# zulu_a7_4.net
KiCad netlist of a schematic drawn in Altium Designer
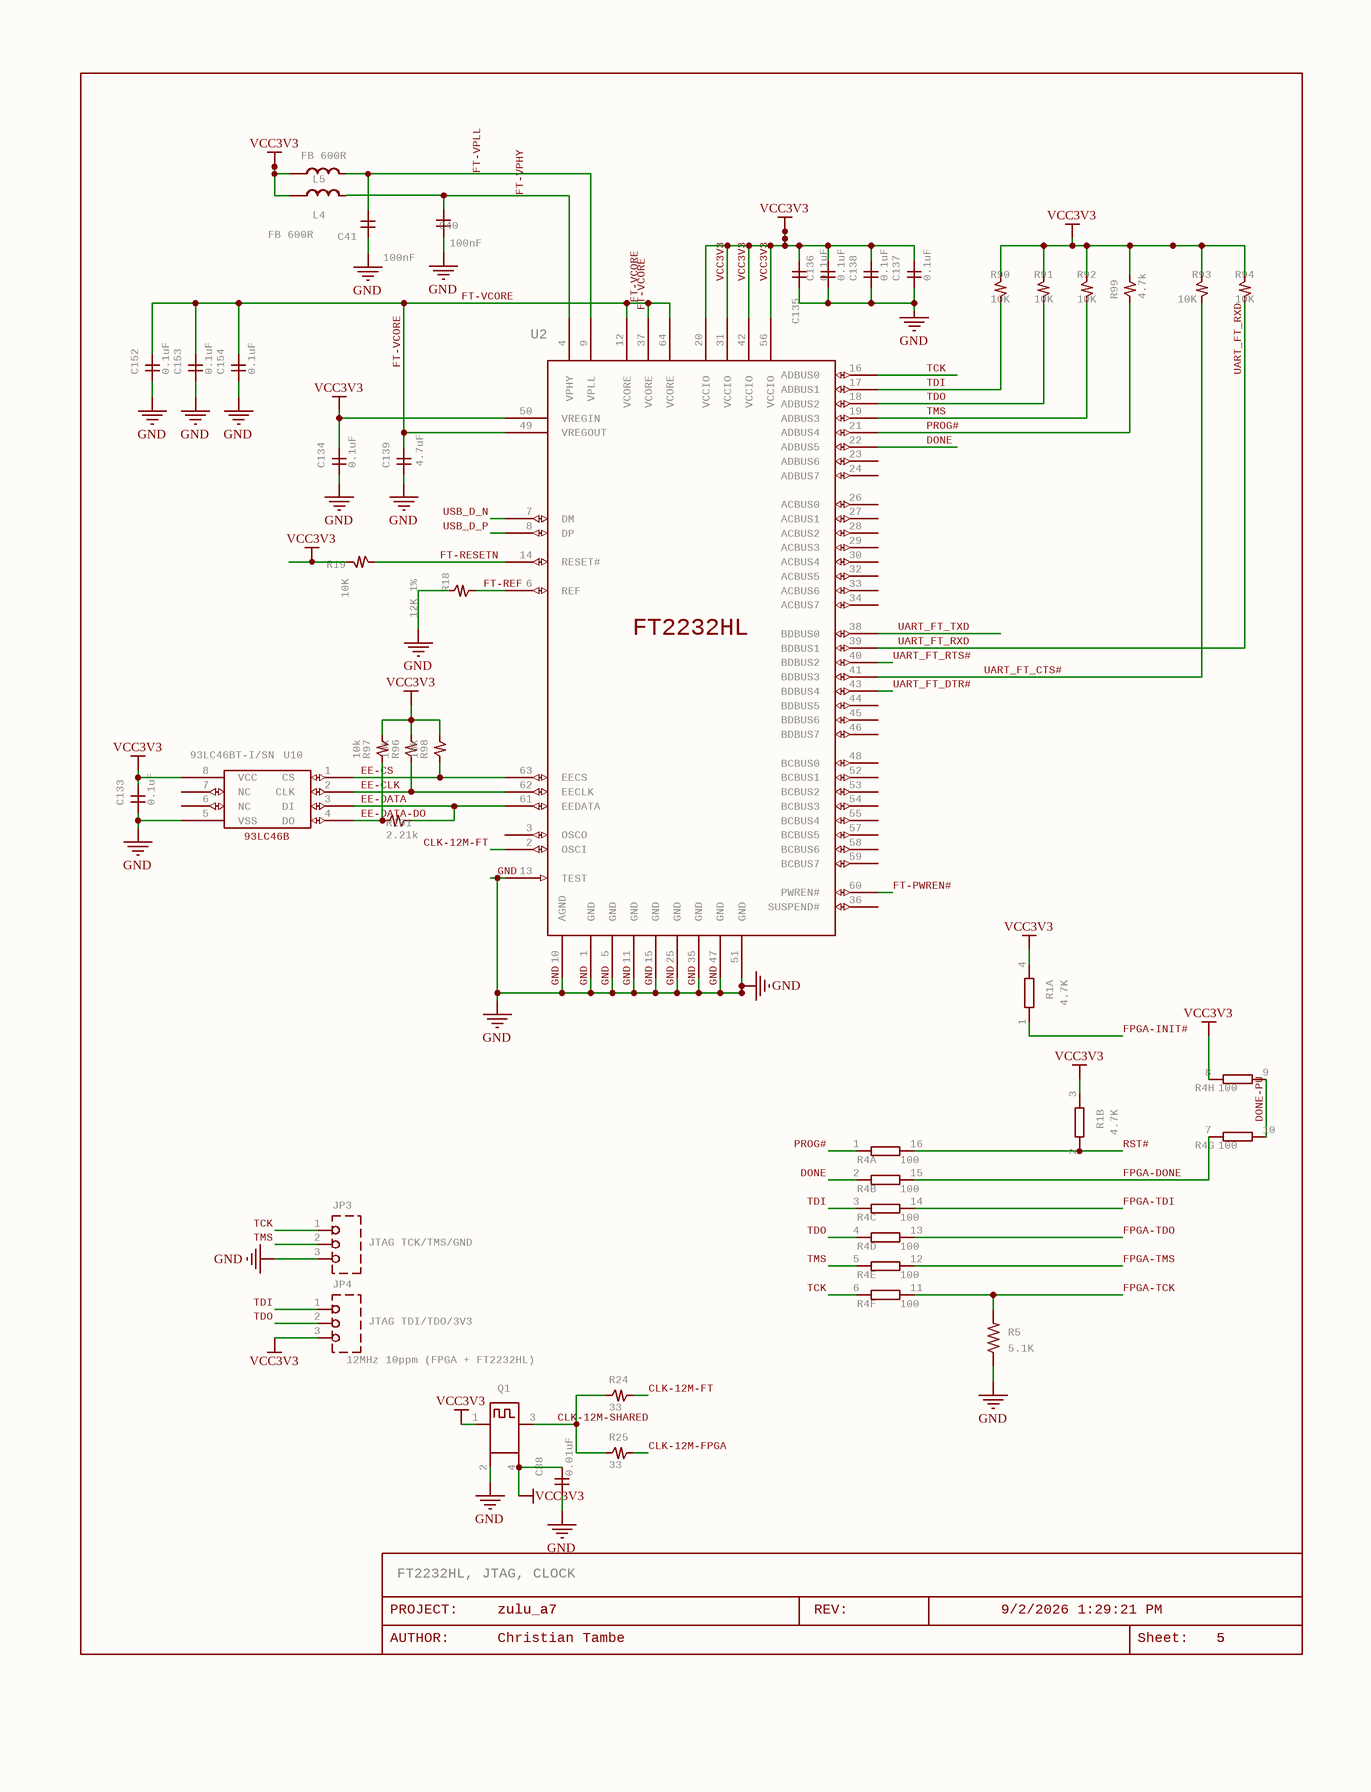
[diagram p0: zulu_a7_4.SchDoc]

(export (version "E")
  (design (tool "Eeschema 10.0.6"))
  (components
    (comp (ref "C38")
      (value "0.01uF")
      (footprint "C0201")
      (description "CAPACITOR, generic non-polarized, horizontal pins")
      (fields (field (name "MANF") "Murata"))
      (libsource (lib "rcl") (part "C-GENERICC0201"))
    )
    (comp (ref "C40")
      (value "100nF")
      (footprint "C0201")
      (description "CAPACITOR, generic non-polarized, horizontal pins")
      (fields (field (name "MANF") "Murata"))
      (libsource (lib "rcl") (part "C-GENERICC0201"))
    )
    (comp (ref "C41")
      (value "100nF")
      (footprint "C0201")
      (description "CAPACITOR, generic non-polarized, horizontal pins")
      (fields (field (name "MANF") "Murata"))
      (libsource (lib "") (part "C-GENERICC0201_2"))
    )
    (comp (ref "C133")
      (value "0.1uF")
      (footprint "C0201")
      (description "CAPACITOR, generic non-polarized, horizontal pins")
      (fields (field (name "MANF") "Murata"))
      (libsource (lib "rcl") (part "C-GENERICC0201"))
    )
    (comp (ref "C134")
      (value "0.1uF")
      (footprint "C0201")
      (description "CAPACITOR, generic non-polarized, horizontal pins")
      (fields (field (name "MANF") "Murata"))
      (libsource (lib "rcl") (part "C-GENERICC0201"))
    )
    (comp (ref "C135")
      (value "0.1uF")
      (footprint "C0201")
      (description "CAPACITOR, generic non-polarized, horizontal pins")
      (fields (field (name "MANF") "Murata"))
      (libsource (lib "rcl") (part "C-GENERICC0201"))
    )
    (comp (ref "C136")
      (value "0.1uF")
      (footprint "C0201")
      (description "CAPACITOR, generic non-polarized, horizontal pins")
      (fields (field (name "MANF") "Murata"))
      (libsource (lib "rcl") (part "C-GENERICC0201"))
    )
    (comp (ref "C137")
      (value "0.1uF")
      (footprint "C0201")
      (description "CAPACITOR, generic non-polarized, horizontal pins")
      (fields (field (name "MANF") "Murata"))
      (libsource (lib "rcl") (part "C-GENERICC0201"))
    )
    (comp (ref "C138")
      (value "0.1uF")
      (footprint "C0201")
      (description "CAPACITOR, generic non-polarized, horizontal pins")
      (fields (field (name "MANF") "Murata"))
      (libsource (lib "rcl") (part "C-GENERICC0201"))
    )
    (comp (ref "C139")
      (value "4.7uF")
      (footprint "C0402")
      (description "CAPACITOR, generic non-polarized, horizontal pins")
      (fields (field (name "MANF") "Taiyo Yuden"))
      (libsource (lib "rcl") (part "C-GENERICC0402"))
    )
    (comp (ref "C152")
      (value "0.1uF")
      (footprint "C0201")
      (description "CAPACITOR, generic non-polarized, horizontal pins")
      (fields (field (name "MANF") "Murata"))
      (libsource (lib "") (part "C-GENERICC0201_1"))
    )
    (comp (ref "C153")
      (value "0.1uF")
      (footprint "C0201")
      (description "CAPACITOR, generic non-polarized, horizontal pins")
      (fields (field (name "MANF") "Murata"))
      (libsource (lib "") (part "C-GENERICC0201_1"))
    )
    (comp (ref "C154")
      (value "0.1uF")
      (footprint "C0201")
      (description "CAPACITOR, generic non-polarized, horizontal pins")
      (fields (field (name "MANF") "Murata"))
      (libsource (lib "") (part "C-GENERICC0201_1"))
    )
    (comp (ref "FRAME4")
      (value "DOCFIELD")
      (description "DOCUMENT FIELD")
      (fields
        (field (name "LAST_DATE_TIME") "9/2/2026 1:29:21 PM")
        (field (name "SHEET") "Sheet:")
        (field (name "SHEET_1") "5")
        (field (name "REV") "REV:")
        (field (name "PROJECT") "PROJECT:")
        (field (name "DRAWING_NAME") "zulu_a7")
        (field (name "AUTHOR") "Christian Tambe")
        (field (name "DRAWING_NAME_1") "zulu_a7")
        (field (name "SHEET_2") "5")
        (field (name "LIBRARYNAME") "ctambe")
      )
      (libsource (lib "ctambe") (part "DOCFIELD"))
    )
    (comp (ref "JP3")
      (value "JTAG TCK/TMS/GND")
      (footprint "1X03-NOSILK")
      (fields (field (name "LIBRARYNAME") "pinhead"))
      (libsource (lib "pinhead") (part "TESTPT-1X3NOSILK"))
    )
    (comp (ref "JP4")
      (value "JTAG TDI/TDO/3V3")
      (footprint "1X03-NOSILK")
      (fields (field (name "LIBRARYNAME") "pinhead"))
      (libsource (lib "pinhead") (part "TESTPT-1X3NOSILK"))
    )
    (comp (ref "L4")
      (value "FB 600R")
      (footprint "IND0603")
      (description "INDUCTOR, generic power inductor")
      (fields (field (name "MANF") "Murata") (field (name "LIBRARYNAME") "ctambe"))
      (libsource (lib "ctambe") (part "INDUCTOR"))
    )
    (comp (ref "L5")
      (value "FB 600R")
      (footprint "IND0603")
      (description "INDUCTOR, generic power inductor")
      (fields (field (name "MANF") "Murata") (field (name "LIBRARYNAME") "ctambe"))
      (libsource (lib "ctambe") (part "INDUCTOR"))
    )
    (comp (ref "Q1")
      (value "12MHz 10ppm (FPGA + FT2232HL)")
      (footprint "32X25")
      (description "Crystal Chip")
      (fields (field (name "MANF") "ECS") (field (name "LIBRARYNAME") "ctambe"))
      (libsource (lib "ctambe") (part "OSC_CHIPASEM1-12MHZ"))
    )
    (comp (ref "R1")
      (value "4.7K")
      (footprint "742C043")
      (description "Resistor 2-pack   Package of two resistors.")
      (fields (field (name "MANF") "CTS") (field (name "LIBRARYNAME") "ctambe"))
      (libsource (lib "ctambe") (part "RES2742"))
    )
    (comp (ref "R4")
      (value "100")
      (footprint "742C163")
      (description "Resistor 8-pack   Package of eight resistors, six used.")
      (fields (field (name "MANF") "CTS") (field (name "LIBRARYNAME") "ctambe"))
      (libsource (lib "ctambe") (part "RES8742"))
    )
    (comp (ref "R5")
      (value "5.1K")
      (footprint "R0201")
      (description "RESISTOR, American symbol")
      (fields (field (name "MANF") "Yageo"))
      (libsource (lib "rcl") (part "R-US_R0201"))
    )
    (comp (ref "R18")
      (value "12K 1%")
      (footprint "R0402")
      (description "RESISTOR, American symbol, small 2-zigzag variant (sheet 2 only)")
      (fields (field (name "MANF") "Yageo"))
      (libsource (lib "rcl") (part "R-US_SMALLR0402"))
    )
    (comp (ref "R19")
      (value "10K")
      (footprint "R0201")
      (description "RESISTOR, American symbol, small 2-zigzag variant (sheet 2 only)")
      (fields (field (name "MANF") "Yageo"))
      (libsource (lib "rcl") (part "R-US_SMALLR0201"))
    )
    (comp (ref "R24")
      (value "33")
      (footprint "R0201")
      (description "RESISTOR, American symbol, small 2-zigzag variant (sheet 2 only)")
      (fields (field (name "MANF") "Yageo"))
      (libsource (lib "rcl") (part "R-US_SMALLR0201"))
    )
    (comp (ref "R25")
      (value "33")
      (footprint "R0201")
      (description "RESISTOR, American symbol, small 2-zigzag variant (sheet 2 only)")
      (fields (field (name "MANF") "Yageo"))
      (libsource (lib "rcl") (part "R-US_SMALLR0201"))
    )
    (comp (ref "R90")
      (value "10K")
      (footprint "R0201")
      (description "RESISTOR, American symbol, small 2-zigzag variant (sheet 2 only)")
      (fields (field (name "MANF") "Yageo"))
      (libsource (lib "rcl") (part "R-US_SMALLR0201"))
    )
    (comp (ref "R91")
      (value "10K")
      (footprint "R0201")
      (description "RESISTOR, American symbol, small 2-zigzag variant (sheet 2 only)")
      (fields (field (name "MANF") "Yageo"))
      (libsource (lib "rcl") (part "R-US_SMALLR0201"))
    )
    (comp (ref "R92")
      (value "10K")
      (footprint "R0201")
      (description "RESISTOR, American symbol, small 2-zigzag variant (sheet 2 only)")
      (fields (field (name "MANF") "Yageo"))
      (libsource (lib "rcl") (part "R-US_SMALLR0201"))
    )
    (comp (ref "R93")
      (value "10K")
      (footprint "R0201")
      (description "RESISTOR, American symbol, small 2-zigzag variant (sheet 2 only)")
      (fields (field (name "MANF") "Yageo"))
      (libsource (lib "rcl") (part "R-US_SMALLR0201"))
    )
    (comp (ref "R94")
      (value "10K")
      (footprint "R0201")
      (description "RESISTOR, American symbol, small 2-zigzag variant (sheet 2 only)")
      (fields (field (name "MANF") "Yageo"))
      (libsource (lib "rcl") (part "R-US_SMALLR0201"))
    )
    (comp (ref "R96")
      (value "10k")
      (footprint "R0201")
      (description "RESISTOR, American symbol, small 2-zigzag variant (sheet 2 only)")
      (fields (field (name "MANF") "Yageo"))
      (libsource (lib "rcl") (part "R-US_SMALLR0201"))
    )
    (comp (ref "R97")
      (value "10k")
      (footprint "R0201")
      (description "RESISTOR, American symbol, small 2-zigzag variant (sheet 2 only)")
      (fields (field (name "MANF") "Yageo"))
      (libsource (lib "rcl") (part "R-US_SMALLR0201"))
    )
    (comp (ref "R98")
      (value "10k")
      (footprint "R0201")
      (description "RESISTOR, American symbol, small 2-zigzag variant (sheet 2 only)")
      (fields (field (name "MANF") "Yageo"))
      (libsource (lib "rcl") (part "R-US_SMALLR0201"))
    )
    (comp (ref "R99")
      (value "4.7k")
      (footprint "R0201")
      (description "RESISTOR, American symbol, small 2-zigzag variant (sheet 2 only)")
      (fields (field (name "MANF") "Yageo"))
      (libsource (lib "rcl") (part "R-US_SMALLR0201"))
    )
    (comp (ref "R101")
      (value "2.21k")
      (footprint "R0201")
      (description "RESISTOR, American symbol, small 2-zigzag variant (sheet 2 only)")
      (fields (field (name "MANF") "Yageo"))
      (libsource (lib "rcl") (part "R-US_SMALLR0201"))
    )
    (comp (ref "U2")
      (value "FT2232HL USB-UART/JTAG Bridge")
      (footprint "FT2232HL-LQFP64")
      (fields
        (field (name "FT2232HL") "FT2232HL")
        (field (name "MANF") "FTDI")
        (field (name "LIBRARYNAME") "ctambe")
      )
      (libsource (lib "ctambe") (part "FT2232HL-LQFP64"))
    )
    (comp (ref "U10")
      (value "93LC46BT-I/SN")
      (footprint "SPI-8_SOIC_150")
      (fields
        (field (name "93LC46B") "93LC46B")
        (field (name "MANF") "Microchip")
        (field (name "LIBRARYNAME") "ctambe")
      )
      (libsource (lib "ctambe") (part "EEPROM-93LC46B-I/SN"))
    )
  )
  (nets
    (net (code "1") (name "/CLK-12M-FPGA") (class "Default")
      (node (ref "R25") (pin "2") (pinfunction "2_2") (pintype "passive"))
    )
    (net (code "2") (name "/CLK-12M-FT") (class "Default")
      (node (ref "R24") (pin "2") (pinfunction "2_2") (pintype "passive"))
      (node (ref "U2") (pin "2") (pinfunction "OSCI_2") (pintype "bidirectional"))
    )
    (net (code "3") (name "/CLK-12M-SHARED") (class "Default")
      (node (ref "Q1") (pin "3") (pinfunction "3_3") (pintype "passive"))
      (node (ref "R24") (pin "1") (pinfunction "1_1") (pintype "passive"))
      (node (ref "R25") (pin "1") (pinfunction "1_1") (pintype "passive"))
    )
    (net (code "4") (name "/DONE") (class "Default")
      (node (ref "R4") (pin "2") (pinfunction "1_2") (pintype "passive"))
      (node (ref "U2") (pin "22") (pinfunction "ADBUS5_22") (pintype "bidirectional"))
    )
    (net (code "5") (name "/DONE-PU") (class "Default")
      (node (ref "R4") (pin "10") (pinfunction "2_10") (pintype "passive"))
      (node (ref "R4") (pin "9") (pinfunction "2_9") (pintype "passive"))
    )
    (net (code "6") (name "/EE-CLK") (class "Default")
      (node (ref "R96") (pin "1") (pinfunction "1_1") (pintype "passive"))
      (node (ref "U10") (pin "2") (pinfunction "CLK_2") (pintype "bidirectional"))
      (node (ref "U2") (pin "62") (pinfunction "EECLK_62") (pintype "bidirectional"))
    )
    (net (code "7") (name "/EE-CS") (class "Default")
      (node (ref "R98") (pin "1") (pinfunction "1_1") (pintype "passive"))
      (node (ref "U10") (pin "1") (pinfunction "CS_1") (pintype "bidirectional"))
      (node (ref "U2") (pin "63") (pinfunction "EECS_63") (pintype "bidirectional"))
    )
    (net (code "8") (name "/EE-DATA") (class "Default")
      (node (ref "R101") (pin "2") (pinfunction "2_2") (pintype "passive"))
      (node (ref "U10") (pin "3") (pinfunction "DI_3") (pintype "bidirectional"))
      (node (ref "U2") (pin "61") (pinfunction "EEDATA_61") (pintype "bidirectional"))
    )
    (net (code "9") (name "/EE-DATA-DO") (class "Default")
      (node (ref "R101") (pin "1") (pinfunction "1_1") (pintype "passive"))
      (node (ref "R97") (pin "1") (pinfunction "1_1") (pintype "passive"))
      (node (ref "U10") (pin "4") (pinfunction "DO_4") (pintype "bidirectional"))
    )
    (net (code "10") (name "/FPGA-DONE") (class "Default")
      (node (ref "R4") (pin "15") (pinfunction "2_15") (pintype "passive"))
      (node (ref "R4") (pin "7") (pinfunction "1_7") (pintype "passive"))
    )
    (net (code "11") (name "/FPGA-INIT#") (class "Default")
      (node (ref "R1") (pin "1") (pinfunction "1_1") (pintype "passive"))
    )
    (net (code "12") (name "/FPGA-TCK") (class "Default")
      (node (ref "R4") (pin "11") (pinfunction "2_11") (pintype "passive"))
      (node (ref "R5") (pin "2") (pinfunction "2_2") (pintype "passive"))
    )
    (net (code "13") (name "/FPGA-TDI") (class "Default")
      (node (ref "R4") (pin "14") (pinfunction "2_14") (pintype "passive"))
    )
    (net (code "14") (name "/FPGA-TDO") (class "Default")
      (node (ref "R4") (pin "13") (pinfunction "2_13") (pintype "passive"))
    )
    (net (code "15") (name "/FPGA-TMS") (class "Default")
      (node (ref "R4") (pin "12") (pinfunction "2_12") (pintype "passive"))
    )
    (net (code "16") (name "/FT-PWREN#") (class "Default")
      (node (ref "U2") (pin "60") (pinfunction "PWREN#_60") (pintype "bidirectional"))
    )
    (net (code "17") (name "/FT-REF") (class "Default")
      (node (ref "R18") (pin "2") (pinfunction "2_2") (pintype "passive"))
      (node (ref "U2") (pin "6") (pinfunction "REF_6") (pintype "bidirectional"))
    )
    (net (code "18") (name "/FT-RESETN") (class "Default")
      (node (ref "R19") (pin "1") (pinfunction "1_1") (pintype "passive"))
      (node (ref "U2") (pin "14") (pinfunction "RESET#_14") (pintype "bidirectional"))
    )
    (net (code "19") (name "/FT-VCORE") (class "Default")
      (node (ref "C139") (pin "2") (pinfunction "2_2") (pintype "passive"))
      (node (ref "C152") (pin "2") (pinfunction "2_2") (pintype "passive"))
      (node (ref "C153") (pin "2") (pinfunction "2_2") (pintype "passive"))
      (node (ref "C154") (pin "2") (pinfunction "2_2") (pintype "passive"))
      (node (ref "U2") (pin "12") (pinfunction "VCORE_12") (pintype "power_in"))
      (node (ref "U2") (pin "37") (pinfunction "VCORE_37") (pintype "power_in"))
      (node (ref "U2") (pin "49") (pinfunction "VREGOUT_49") (pintype "power_in"))
      (node (ref "U2") (pin "64") (pinfunction "VCORE_64") (pintype "power_in"))
    )
    (net (code "20") (name "/FT-VPHY") (class "Default")
      (node (ref "C40") (pin "2") (pinfunction "2_2") (pintype "passive"))
      (node (ref "L4") (pin "1") (pinfunction "1_1") (pintype "passive"))
      (node (ref "U2") (pin "4") (pinfunction "VPHY_4") (pintype "power_in"))
    )
    (net (code "21") (name "/FT-VPLL") (class "Default")
      (node (ref "C41") (pin "2") (pinfunction "2_2") (pintype "passive"))
      (node (ref "L5") (pin "1") (pinfunction "1_1") (pintype "passive"))
      (node (ref "U2") (pin "9") (pinfunction "VPLL_9") (pintype "power_in"))
    )
    (net (code "22") (name "/PROG#") (class "Default")
      (node (ref "R4") (pin "1") (pinfunction "1_1") (pintype "passive"))
      (node (ref "R99") (pin "1") (pinfunction "1_1") (pintype "passive"))
      (node (ref "U2") (pin "21") (pinfunction "ADBUS4_21") (pintype "bidirectional"))
    )
    (net (code "23") (name "/RST#") (class "Default")
      (node (ref "R1") (pin "2") (pinfunction "1_2") (pintype "passive"))
      (node (ref "R4") (pin "16") (pinfunction "2_16") (pintype "passive"))
    )
    (net (code "24") (name "/TCK") (class "Default")
      (node (ref "JP3") (pin "1") (pinfunction "1_1") (pintype "passive"))
      (node (ref "R4") (pin "6") (pinfunction "1_6") (pintype "passive"))
      (node (ref "U2") (pin "16") (pinfunction "ADBUS0_16") (pintype "bidirectional"))
    )
    (net (code "25") (name "/TDI") (class "Default")
      (node (ref "JP4") (pin "1") (pinfunction "1_1") (pintype "passive"))
      (node (ref "R4") (pin "3") (pinfunction "1_3") (pintype "passive"))
      (node (ref "R90") (pin "1") (pinfunction "1_1") (pintype "passive"))
      (node (ref "U2") (pin "17") (pinfunction "ADBUS1_17") (pintype "bidirectional"))
    )
    (net (code "26") (name "/TDO") (class "Default")
      (node (ref "JP4") (pin "2") (pinfunction "2_2") (pintype "passive"))
      (node (ref "R4") (pin "4") (pinfunction "1_4") (pintype "passive"))
      (node (ref "R91") (pin "1") (pinfunction "1_1") (pintype "passive"))
      (node (ref "U2") (pin "18") (pinfunction "ADBUS2_18") (pintype "bidirectional"))
    )
    (net (code "27") (name "/TMS") (class "Default")
      (node (ref "JP3") (pin "2") (pinfunction "2_2") (pintype "passive"))
      (node (ref "R4") (pin "5") (pinfunction "1_5") (pintype "passive"))
      (node (ref "R92") (pin "1") (pinfunction "1_1") (pintype "passive"))
      (node (ref "U2") (pin "19") (pinfunction "ADBUS3_19") (pintype "bidirectional"))
    )
    (net (code "28") (name "/UART_FT_CTS#") (class "Default")
      (node (ref "R93") (pin "1") (pinfunction "1_1") (pintype "passive"))
      (node (ref "U2") (pin "41") (pinfunction "BDBUS3_41") (pintype "bidirectional"))
    )
    (net (code "29") (name "/UART_FT_DTR#") (class "Default")
      (node (ref "U2") (pin "43") (pinfunction "BDBUS4_43") (pintype "bidirectional"))
    )
    (net (code "30") (name "/UART_FT_RTS#") (class "Default")
      (node (ref "U2") (pin "40") (pinfunction "BDBUS2_40") (pintype "bidirectional"))
    )
    (net (code "31") (name "/UART_FT_RXD") (class "Default")
      (node (ref "R94") (pin "1") (pinfunction "1_1") (pintype "passive"))
      (node (ref "U2") (pin "39") (pinfunction "BDBUS1_39") (pintype "bidirectional"))
    )
    (net (code "32") (name "/UART_FT_TXD") (class "Default")
      (node (ref "U2") (pin "38") (pinfunction "BDBUS0_38") (pintype "bidirectional"))
    )
    (net (code "33") (name "/USB_D_N") (class "Default")
      (node (ref "U2") (pin "7") (pinfunction "DM_7") (pintype "bidirectional"))
    )
    (net (code "34") (name "/USB_D_P") (class "Default")
      (node (ref "U2") (pin "8") (pinfunction "DP_8") (pintype "bidirectional"))
    )
    (net (code "35") (name "GND") (class "Default")
      (node (ref "C133") (pin "1") (pinfunction "1_1") (pintype "passive"))
      (node (ref "C134") (pin "1") (pinfunction "1_1") (pintype "passive"))
      (node (ref "C135") (pin "1") (pinfunction "1_1") (pintype "passive"))
      (node (ref "C136") (pin "1") (pinfunction "1_1") (pintype "passive"))
      (node (ref "C137") (pin "1") (pinfunction "1_1") (pintype "passive"))
      (node (ref "C138") (pin "1") (pinfunction "1_1") (pintype "passive"))
      (node (ref "C139") (pin "1") (pinfunction "1_1") (pintype "passive"))
      (node (ref "C152") (pin "1") (pinfunction "1_1") (pintype "passive"))
      (node (ref "C153") (pin "1") (pinfunction "1_1") (pintype "passive"))
      (node (ref "C154") (pin "1") (pinfunction "1_1") (pintype "passive"))
      (node (ref "C38") (pin "1") (pinfunction "1_1") (pintype "passive"))
      (node (ref "C40") (pin "1") (pinfunction "1_1") (pintype "passive"))
      (node (ref "C41") (pin "1") (pinfunction "1_1") (pintype "passive"))
      (node (ref "JP3") (pin "3") (pinfunction "3_3") (pintype "passive"))
      (node (ref "Q1") (pin "2") (pinfunction "2_2") (pintype "passive"))
      (node (ref "R18") (pin "1") (pinfunction "1_1") (pintype "passive"))
      (node (ref "R5") (pin "1") (pinfunction "1_1") (pintype "passive"))
      (node (ref "U10") (pin "5") (pinfunction "VSS_5") (pintype "power_in"))
      (node (ref "U2") (pin "1") (pinfunction "GND_1") (pintype "power_in"))
      (node (ref "U2") (pin "10") (pinfunction "AGND_10") (pintype "power_in"))
      (node (ref "U2") (pin "11") (pinfunction "GND_11") (pintype "power_in"))
      (node (ref "U2") (pin "13") (pinfunction "TEST_13") (pintype "input"))
      (node (ref "U2") (pin "15") (pinfunction "GND_15") (pintype "power_in"))
      (node (ref "U2") (pin "25") (pinfunction "GND_25") (pintype "power_in"))
      (node (ref "U2") (pin "35") (pinfunction "GND_35") (pintype "power_in"))
      (node (ref "U2") (pin "47") (pinfunction "GND_47") (pintype "power_in"))
      (node (ref "U2") (pin "5") (pinfunction "GND_5") (pintype "power_in"))
      (node (ref "U2") (pin "51") (pinfunction "GND_51") (pintype "power_in"))
    )
    (net (code "36") (name "VCC3V3") (class "Default")
      (node (ref "C133") (pin "2") (pinfunction "2_2") (pintype "passive"))
      (node (ref "C134") (pin "2") (pinfunction "2_2") (pintype "passive"))
      (node (ref "C135") (pin "2") (pinfunction "2_2") (pintype "passive"))
      (node (ref "C136") (pin "2") (pinfunction "2_2") (pintype "passive"))
      (node (ref "C137") (pin "2") (pinfunction "2_2") (pintype "passive"))
      (node (ref "C138") (pin "2") (pinfunction "2_2") (pintype "passive"))
      (node (ref "C38") (pin "2") (pinfunction "2_2") (pintype "passive"))
      (node (ref "JP4") (pin "3") (pinfunction "3_3") (pintype "passive"))
      (node (ref "L4") (pin "2") (pinfunction "2_2") (pintype "passive"))
      (node (ref "L5") (pin "2") (pinfunction "2_2") (pintype "passive"))
      (node (ref "Q1") (pin "1") (pinfunction "1_1") (pintype "passive"))
      (node (ref "Q1") (pin "4") (pinfunction "4_4") (pintype "passive"))
      (node (ref "R1") (pin "3") (pinfunction "2_3") (pintype "passive"))
      (node (ref "R1") (pin "4") (pinfunction "2_4") (pintype "passive"))
      (node (ref "R19") (pin "2") (pinfunction "2_2") (pintype "passive"))
      (node (ref "R4") (pin "8") (pinfunction "1_8") (pintype "passive"))
      (node (ref "R90") (pin "2") (pinfunction "2_2") (pintype "passive"))
      (node (ref "R91") (pin "2") (pinfunction "2_2") (pintype "passive"))
      (node (ref "R92") (pin "2") (pinfunction "2_2") (pintype "passive"))
      (node (ref "R93") (pin "2") (pinfunction "2_2") (pintype "passive"))
      (node (ref "R94") (pin "2") (pinfunction "2_2") (pintype "passive"))
      (node (ref "R96") (pin "2") (pinfunction "2_2") (pintype "passive"))
      (node (ref "R97") (pin "2") (pinfunction "2_2") (pintype "passive"))
      (node (ref "R98") (pin "2") (pinfunction "2_2") (pintype "passive"))
      (node (ref "R99") (pin "2") (pinfunction "2_2") (pintype "passive"))
      (node (ref "U10") (pin "8") (pinfunction "VCC_8") (pintype "power_in"))
      (node (ref "U2") (pin "20") (pinfunction "VCCIO_20") (pintype "power_in"))
      (node (ref "U2") (pin "31") (pinfunction "VCCIO_31") (pintype "power_in"))
      (node (ref "U2") (pin "42") (pinfunction "VCCIO_42") (pintype "power_in"))
      (node (ref "U2") (pin "50") (pinfunction "VREGIN_50") (pintype "power_in"))
      (node (ref "U2") (pin "56") (pinfunction "VCCIO_56") (pintype "power_in"))
    )
    (net (code "37") (name "unconnected-(U2-ACBUS0-Pad26)") (class "Default")
      (node (ref "U2") (pin "26") (pinfunction "ACBUS0_26") (pintype "bidirectional"))
    )
    (net (code "38") (name "unconnected-(U2-ACBUS1-Pad27)") (class "Default")
      (node (ref "U2") (pin "27") (pinfunction "ACBUS1_27") (pintype "bidirectional"))
    )
    (net (code "39") (name "unconnected-(U2-ACBUS2-Pad28)") (class "Default")
      (node (ref "U2") (pin "28") (pinfunction "ACBUS2_28") (pintype "bidirectional"))
    )
    (net (code "40") (name "unconnected-(U2-ACBUS3-Pad29)") (class "Default")
      (node (ref "U2") (pin "29") (pinfunction "ACBUS3_29") (pintype "bidirectional"))
    )
    (net (code "41") (name "unconnected-(U2-ACBUS4-Pad30)") (class "Default")
      (node (ref "U2") (pin "30") (pinfunction "ACBUS4_30") (pintype "bidirectional"))
    )
    (net (code "42") (name "unconnected-(U2-ACBUS5-Pad32)") (class "Default")
      (node (ref "U2") (pin "32") (pinfunction "ACBUS5_32") (pintype "bidirectional"))
    )
    (net (code "43") (name "unconnected-(U2-ACBUS6-Pad33)") (class "Default")
      (node (ref "U2") (pin "33") (pinfunction "ACBUS6_33") (pintype "bidirectional"))
    )
    (net (code "44") (name "unconnected-(U2-ACBUS7-Pad34)") (class "Default")
      (node (ref "U2") (pin "34") (pinfunction "ACBUS7_34") (pintype "bidirectional"))
    )
    (net (code "45") (name "unconnected-(U2-ADBUS6-Pad23)") (class "Default")
      (node (ref "U2") (pin "23") (pinfunction "ADBUS6_23") (pintype "bidirectional"))
    )
    (net (code "46") (name "unconnected-(U2-ADBUS7-Pad24)") (class "Default")
      (node (ref "U2") (pin "24") (pinfunction "ADBUS7_24") (pintype "bidirectional"))
    )
    (net (code "47") (name "unconnected-(U2-BCBUS0-Pad48)") (class "Default")
      (node (ref "U2") (pin "48") (pinfunction "BCBUS0_48") (pintype "bidirectional"))
    )
    (net (code "48") (name "unconnected-(U2-BCBUS1-Pad52)") (class "Default")
      (node (ref "U2") (pin "52") (pinfunction "BCBUS1_52") (pintype "bidirectional"))
    )
    (net (code "49") (name "unconnected-(U2-BCBUS2-Pad53)") (class "Default")
      (node (ref "U2") (pin "53") (pinfunction "BCBUS2_53") (pintype "bidirectional"))
    )
    (net (code "50") (name "unconnected-(U2-BCBUS3-Pad54)") (class "Default")
      (node (ref "U2") (pin "54") (pinfunction "BCBUS3_54") (pintype "bidirectional"))
    )
    (net (code "51") (name "unconnected-(U2-BCBUS4-Pad55)") (class "Default")
      (node (ref "U2") (pin "55") (pinfunction "BCBUS4_55") (pintype "bidirectional"))
    )
    (net (code "52") (name "unconnected-(U2-BCBUS5-Pad57)") (class "Default")
      (node (ref "U2") (pin "57") (pinfunction "BCBUS5_57") (pintype "bidirectional"))
    )
    (net (code "53") (name "unconnected-(U2-BCBUS6-Pad58)") (class "Default")
      (node (ref "U2") (pin "58") (pinfunction "BCBUS6_58") (pintype "bidirectional"))
    )
    (net (code "54") (name "unconnected-(U2-BCBUS7-Pad59)") (class "Default")
      (node (ref "U2") (pin "59") (pinfunction "BCBUS7_59") (pintype "bidirectional"))
    )
    (net (code "55") (name "unconnected-(U2-BDBUS5-Pad44)") (class "Default")
      (node (ref "U2") (pin "44") (pinfunction "BDBUS5_44") (pintype "bidirectional"))
    )
    (net (code "56") (name "unconnected-(U2-BDBUS6-Pad45)") (class "Default")
      (node (ref "U2") (pin "45") (pinfunction "BDBUS6_45") (pintype "bidirectional"))
    )
    (net (code "57") (name "unconnected-(U2-BDBUS7-Pad46)") (class "Default")
      (node (ref "U2") (pin "46") (pinfunction "BDBUS7_46") (pintype "bidirectional"))
    )
    (net (code "58") (name "unconnected-(U2-OSCO-Pad3)") (class "Default")
      (node (ref "U2") (pin "3") (pinfunction "OSCO_3") (pintype "bidirectional"))
    )
    (net (code "59") (name "unconnected-(U2-SUSPEND#-Pad36)") (class "Default")
      (node (ref "U2") (pin "36") (pinfunction "SUSPEND#_36") (pintype "bidirectional"))
    )
    (net (code "60") (name "unconnected-(U10-NC-Pad6)") (class "Default")
      (node (ref "U10") (pin "6") (pinfunction "NC_6") (pintype "bidirectional"))
    )
    (net (code "61") (name "unconnected-(U10-NC-Pad7)") (class "Default")
      (node (ref "U10") (pin "7") (pinfunction "NC_7") (pintype "bidirectional"))
    )
  )
)
